# CheetahStack.net
KiCad netlist of a schematic drawn in Altium Designer
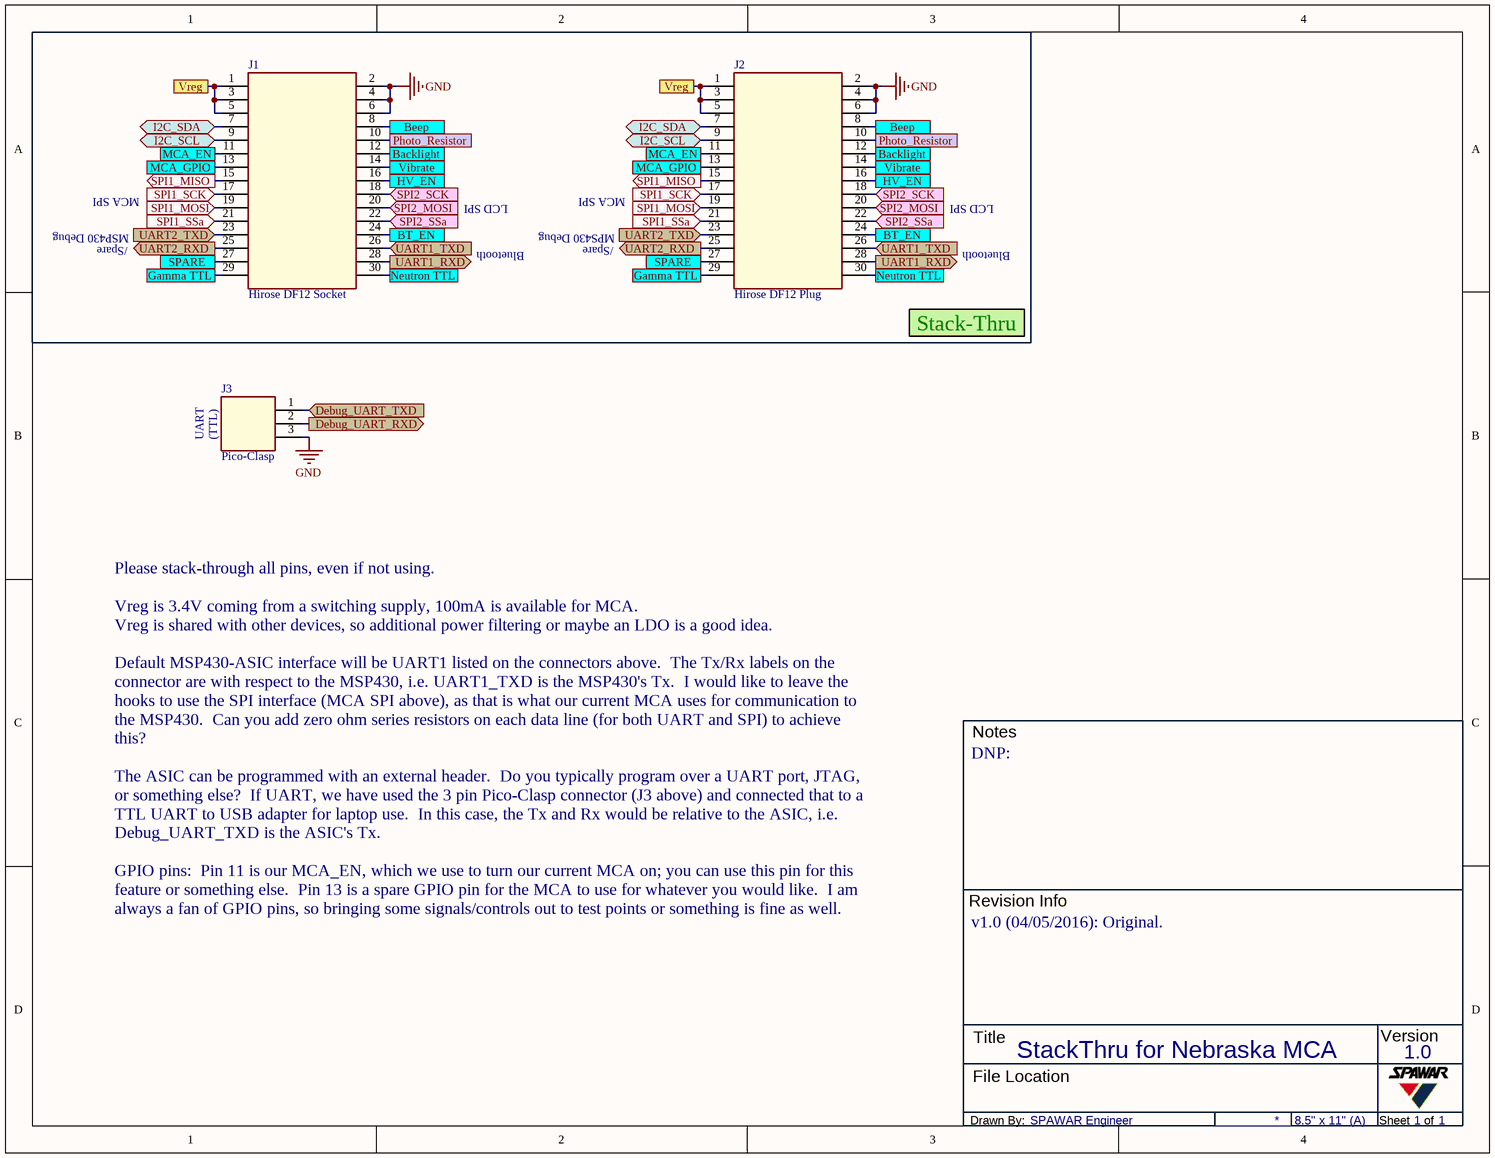
[diagram p0: CheetahStack.SchDoc]

(export (version "E")
  (design (tool "Eeschema 10.0.6"))
  (components
    (comp (ref "J1")
      (value "Hirose DF12 Socket")
      (footprint "DF12B-30DS-0.5V(86)")
      (description "Conn, Hirose, 2x15 Pin, DF12, Socket, Vert, SMT, with metal fitting")
      (fields (field (name "DIST PART") "798-DF12B30DS05V86") (field (name "MANUFACTURER") "Hirose"))
      (libsource (lib "ALTIUM_SCH_LIBRARY_SIMMONS") (part "Conn, Hirose, 2x15 Pin, DF12, Socket, Vert, SMT, with metal fitting"))
    )
    (comp (ref "J2")
      (value "Hirose DF12 Plug")
      (footprint "DF12B(5.0)-30DP-0.5V(86)")
      (description "Conn, Hirose, 2x15 Pin, DF12, Plug, Vert, SMT, 5.0mm, with metal fitting")
      (fields (field (name "DIST PART") "798-DF12B5030DP05V86") (field (name "MANUFACTURER") "Hirose"))
      (libsource (lib "ALTIUM_SCH_LIBRARY_SIMMONS") (part "Conn, Hirose, 2x15 Pin, DF12, Plug, Vert, SMT, 5.0mm, with metal fitting"))
    )
    (comp (ref "J3")
      (value "Pico-Clasp")
      (footprint "Molex 1x3 Pin, Pico-Clasp")
      (description "Conn, Molex, 1x3 Pin, Pico-Clasp, Horz")
      (fields (field (name "DIST PART") "WM7894CT-ND") (field (name "MANUFACTURER") "Molex"))
      (libsource (lib "ALTIUM_SCH_LIBRARY_SIMMONS") (part "Conn, Molex, 1x3 Pin, Pico-Clasp, Horz"))
    )
  )
  (nets
    (net (code "1") (name "/BT_EN") (class "Default")
      (node (ref "J1") (pin "24") (pinfunction "24_24") (pintype "passive"))
      (node (ref "J2") (pin "24") (pinfunction "24_24") (pintype "passive"))
    )
    (net (code "2") (name "/Backlight") (class "Default")
      (node (ref "J1") (pin "12") (pinfunction "12_12") (pintype "passive"))
      (node (ref "J2") (pin "12") (pinfunction "12_12") (pintype "passive"))
    )
    (net (code "3") (name "/Beep") (class "Default")
      (node (ref "J1") (pin "8") (pinfunction "8_8") (pintype "passive"))
      (node (ref "J2") (pin "8") (pinfunction "8_8") (pintype "passive"))
    )
    (net (code "4") (name "/Debug_UART_RXD") (class "Default")
      (node (ref "J3") (pin "2") (pinfunction "2_2") (pintype "passive"))
    )
    (net (code "5") (name "/Debug_UART_TXD") (class "Default")
      (node (ref "J3") (pin "1") (pinfunction "1_1") (pintype "passive"))
    )
    (net (code "6") (name "/Gamma TTL") (class "Default")
      (node (ref "J1") (pin "29") (pinfunction "29_29") (pintype "passive"))
      (node (ref "J2") (pin "29") (pinfunction "29_29") (pintype "passive"))
    )
    (net (code "7") (name "/HV_EN") (class "Default")
      (node (ref "J1") (pin "16") (pinfunction "16_16") (pintype "passive"))
      (node (ref "J2") (pin "16") (pinfunction "16_16") (pintype "passive"))
    )
    (net (code "8") (name "/I2C_SCL") (class "Default")
      (node (ref "J1") (pin "9") (pinfunction "9_9") (pintype "passive"))
      (node (ref "J2") (pin "9") (pinfunction "9_9") (pintype "passive"))
    )
    (net (code "9") (name "/I2C_SDA") (class "Default")
      (node (ref "J1") (pin "7") (pinfunction "7_7") (pintype "passive"))
      (node (ref "J2") (pin "7") (pinfunction "7_7") (pintype "passive"))
    )
    (net (code "10") (name "/MCA_EN") (class "Default")
      (node (ref "J1") (pin "11") (pinfunction "11_11") (pintype "passive"))
      (node (ref "J2") (pin "11") (pinfunction "11_11") (pintype "passive"))
    )
    (net (code "11") (name "/MCA_GPIO") (class "Default")
      (node (ref "J1") (pin "13") (pinfunction "13_13") (pintype "passive"))
      (node (ref "J2") (pin "13") (pinfunction "13_13") (pintype "passive"))
    )
    (net (code "12") (name "/Neutron TTL") (class "Default")
      (node (ref "J1") (pin "30") (pinfunction "30_30") (pintype "passive"))
      (node (ref "J2") (pin "30") (pinfunction "30_30") (pintype "passive"))
    )
    (net (code "13") (name "/Photo_Resistor") (class "Default")
      (node (ref "J1") (pin "10") (pinfunction "10_10") (pintype "passive"))
      (node (ref "J2") (pin "10") (pinfunction "10_10") (pintype "passive"))
    )
    (net (code "14") (name "/SPARE") (class "Default")
      (node (ref "J1") (pin "27") (pinfunction "27_27") (pintype "passive"))
      (node (ref "J2") (pin "27") (pinfunction "27_27") (pintype "passive"))
    )
    (net (code "15") (name "/SPI1_MISO") (class "Default")
      (node (ref "J1") (pin "15") (pinfunction "15_15") (pintype "passive"))
      (node (ref "J2") (pin "15") (pinfunction "15_15") (pintype "passive"))
    )
    (net (code "16") (name "/SPI1_MOSI") (class "Default")
      (node (ref "J1") (pin "19") (pinfunction "19_19") (pintype "passive"))
      (node (ref "J2") (pin "19") (pinfunction "19_19") (pintype "passive"))
    )
    (net (code "17") (name "/SPI1_SCK") (class "Default")
      (node (ref "J1") (pin "17") (pinfunction "17_17") (pintype "passive"))
      (node (ref "J2") (pin "17") (pinfunction "17_17") (pintype "passive"))
    )
    (net (code "18") (name "/SPI1_SSa") (class "Default")
      (node (ref "J1") (pin "21") (pinfunction "21_21") (pintype "passive"))
      (node (ref "J2") (pin "21") (pinfunction "21_21") (pintype "passive"))
    )
    (net (code "19") (name "/SPI2_MOSI") (class "Default")
      (node (ref "J1") (pin "20") (pinfunction "20_20") (pintype "passive"))
      (node (ref "J2") (pin "20") (pinfunction "20_20") (pintype "passive"))
    )
    (net (code "20") (name "/SPI2_SCK") (class "Default")
      (node (ref "J1") (pin "18") (pinfunction "18_18") (pintype "passive"))
      (node (ref "J2") (pin "18") (pinfunction "18_18") (pintype "passive"))
    )
    (net (code "21") (name "/SPI2_SSa") (class "Default")
      (node (ref "J1") (pin "22") (pinfunction "22_22") (pintype "passive"))
      (node (ref "J2") (pin "22") (pinfunction "22_22") (pintype "passive"))
    )
    (net (code "22") (name "/UART1_RXD") (class "Default")
      (node (ref "J1") (pin "28") (pinfunction "28_28") (pintype "passive"))
      (node (ref "J2") (pin "28") (pinfunction "28_28") (pintype "passive"))
    )
    (net (code "23") (name "/UART1_TXD") (class "Default")
      (node (ref "J1") (pin "26") (pinfunction "26_26") (pintype "passive"))
      (node (ref "J2") (pin "26") (pinfunction "26_26") (pintype "passive"))
    )
    (net (code "24") (name "/UART2_RXD") (class "Default")
      (node (ref "J1") (pin "25") (pinfunction "25_25") (pintype "passive"))
      (node (ref "J2") (pin "25") (pinfunction "25_25") (pintype "passive"))
    )
    (net (code "25") (name "/UART2_TXD") (class "Default")
      (node (ref "J1") (pin "23") (pinfunction "23_23") (pintype "passive"))
      (node (ref "J2") (pin "23") (pinfunction "23_23") (pintype "passive"))
    )
    (net (code "26") (name "/Vibrate") (class "Default")
      (node (ref "J1") (pin "14") (pinfunction "14_14") (pintype "passive"))
      (node (ref "J2") (pin "14") (pinfunction "14_14") (pintype "passive"))
    )
    (net (code "27") (name "/Vreg") (class "Default")
      (node (ref "J1") (pin "1") (pinfunction "1_1") (pintype "passive"))
      (node (ref "J1") (pin "3") (pinfunction "3_3") (pintype "passive"))
      (node (ref "J1") (pin "5") (pinfunction "5_5") (pintype "passive"))
      (node (ref "J2") (pin "1") (pinfunction "1_1") (pintype "passive"))
      (node (ref "J2") (pin "3") (pinfunction "3_3") (pintype "passive"))
      (node (ref "J2") (pin "5") (pinfunction "5_5") (pintype "passive"))
    )
    (net (code "28") (name "GND") (class "Default")
      (node (ref "J1") (pin "2") (pinfunction "2_2") (pintype "passive"))
      (node (ref "J1") (pin "4") (pinfunction "4_4") (pintype "passive"))
      (node (ref "J1") (pin "6") (pinfunction "6_6") (pintype "passive"))
      (node (ref "J2") (pin "2") (pinfunction "2_2") (pintype "passive"))
      (node (ref "J2") (pin "4") (pinfunction "4_4") (pintype "passive"))
      (node (ref "J2") (pin "6") (pinfunction "6_6") (pintype "passive"))
      (node (ref "J3") (pin "3") (pinfunction "3_3") (pintype "passive"))
    )
  )
)
